# ethernet_chip.net
KiCad netlist of a schematic drawn in EAGLE
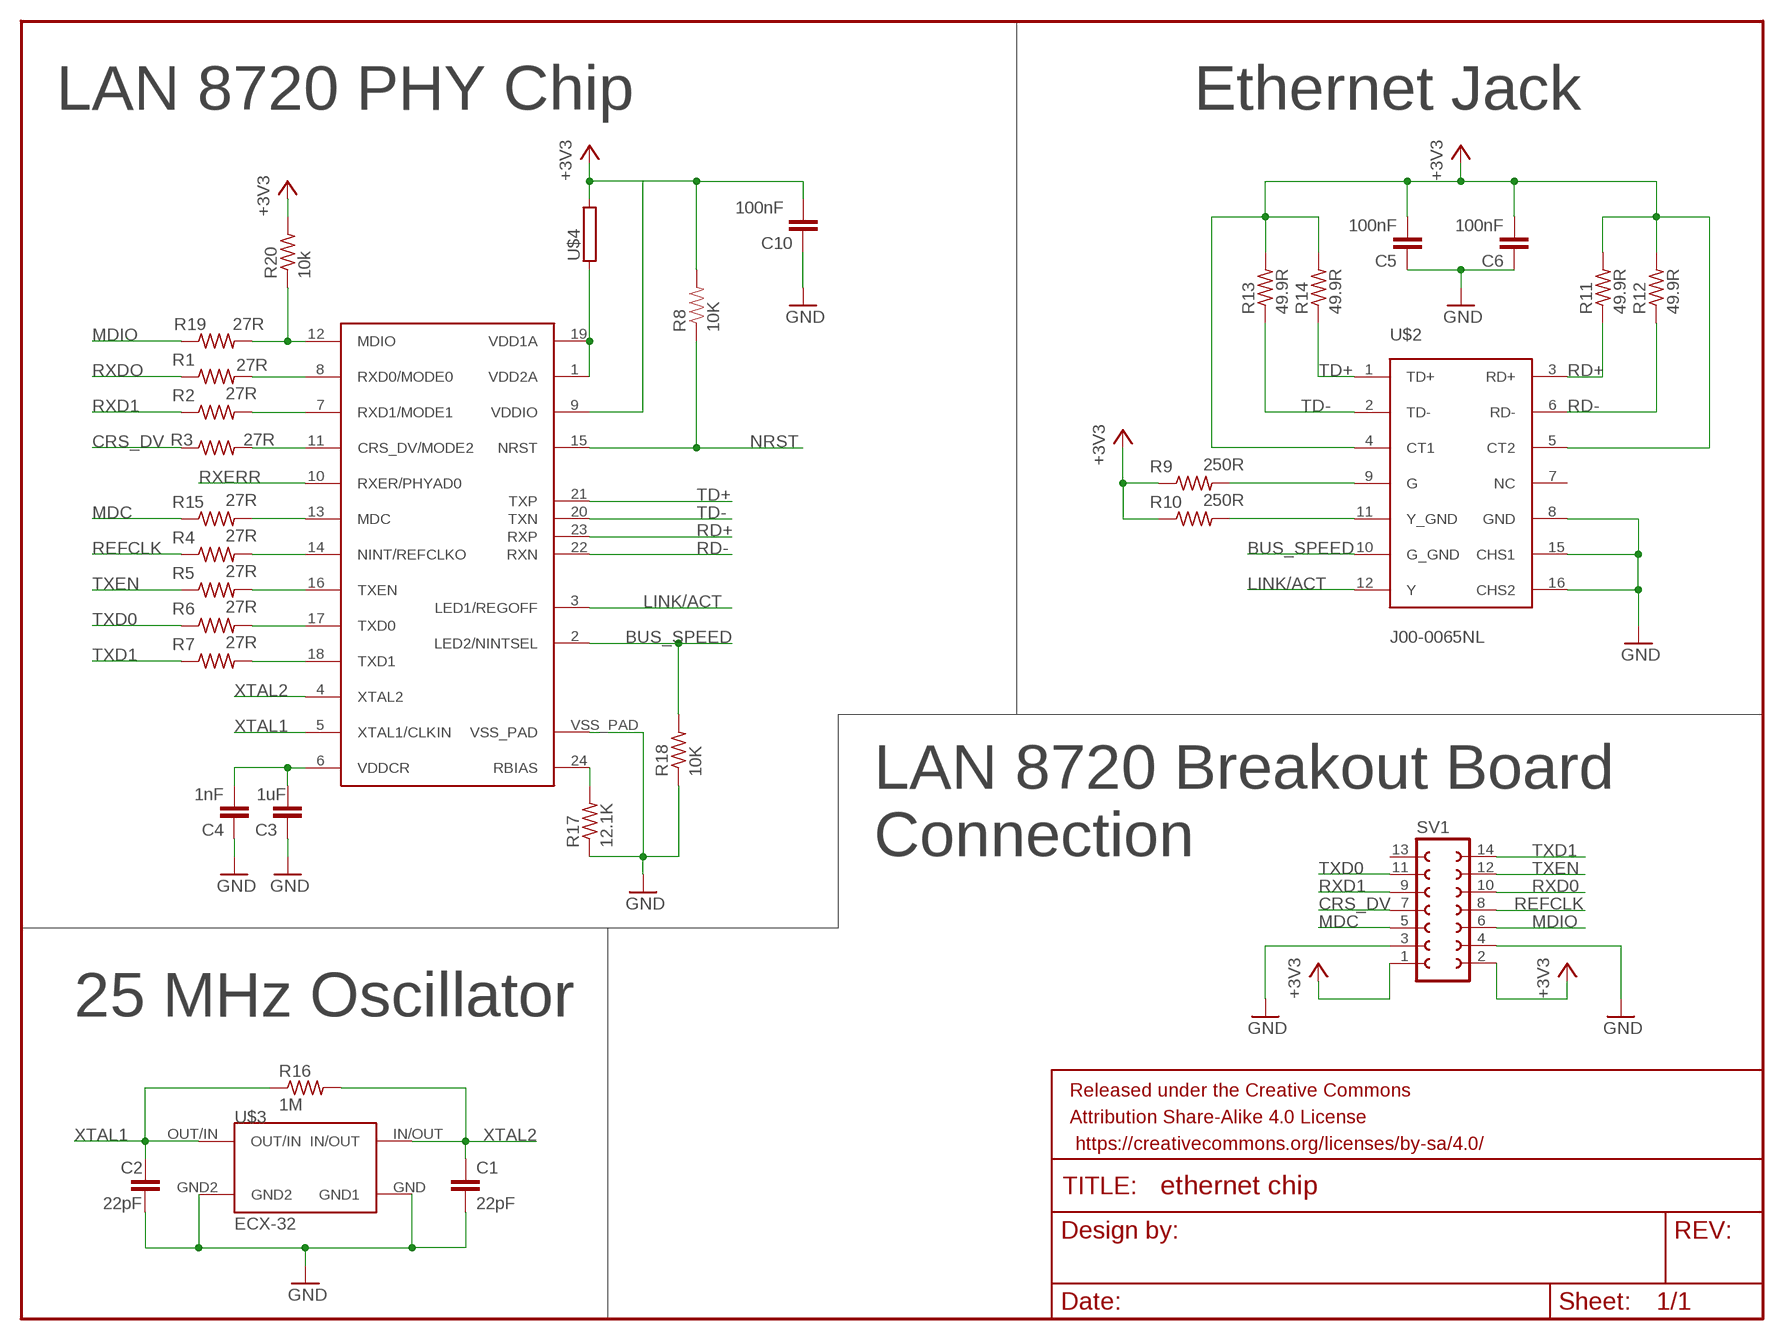
[diagram p0: schematic, sheet 1]

(export (version "E")
  (design (tool "Eeschema 10.0.6"))
  (components
    (comp (ref "C1")
      (value "22pF")
      (footprint "eagle-import:C0603")
      (libsource (lib "eagle-import") (part "CC0603"))
    )
    (comp (ref "C2")
      (value "22pF")
      (footprint "eagle-import:C0603")
      (libsource (lib "eagle-import") (part "CC0603"))
    )
    (comp (ref "C3")
      (value "1uF")
      (footprint "eagle-import:C0603")
      (libsource (lib "eagle-import") (part "CC0603"))
    )
    (comp (ref "C4")
      (value "1nF")
      (footprint "eagle-import:C0603")
      (libsource (lib "eagle-import") (part "CC0603"))
    )
    (comp (ref "C5")
      (value "100nF")
      (footprint "eagle-import:C0603")
      (libsource (lib "eagle-import") (part "CC0603"))
    )
    (comp (ref "C6")
      (value "100nF")
      (footprint "eagle-import:C0603")
      (libsource (lib "eagle-import") (part "CC0603"))
    )
    (comp (ref "C10")
      (value "100nF")
      (footprint "eagle-import:C0603")
      (libsource (lib "eagle-import") (part "CC0603"))
    )
    (comp (ref "FRAME1")
      (value "FRAME-LETTER")
      (footprint "eagle-import:CREATIVE_COMMONS")
      (libsource (lib "eagle-import") (part "FRAME-LETTER"))
    )
    (comp (ref "R1")
      (value "27R")
      (footprint "eagle-import:R0603")
      (libsource (lib "eagle-import") (part "R-US_R0603"))
    )
    (comp (ref "R2")
      (value "27R")
      (footprint "eagle-import:R0603")
      (libsource (lib "eagle-import") (part "R-US_R0603"))
    )
    (comp (ref "R3")
      (value "27R")
      (footprint "eagle-import:R0603")
      (libsource (lib "eagle-import") (part "R-US_R0603"))
    )
    (comp (ref "R4")
      (value "27R")
      (footprint "eagle-import:R0603")
      (libsource (lib "eagle-import") (part "R-US_R0603"))
    )
    (comp (ref "R5")
      (value "27R")
      (footprint "eagle-import:R0603")
      (libsource (lib "eagle-import") (part "R-US_R0603"))
    )
    (comp (ref "R6")
      (value "27R")
      (footprint "eagle-import:R0603")
      (libsource (lib "eagle-import") (part "R-US_R0603"))
    )
    (comp (ref "R7")
      (value "27R")
      (footprint "eagle-import:R0603")
      (libsource (lib "eagle-import") (part "R-US_R0603"))
    )
    (comp (ref "R8")
      (value "10K")
      (footprint "eagle-import:0603-RES")
      (libsource (lib "eagle-import") (part "RESISTOR0603-RES"))
    )
    (comp (ref "R9")
      (value "250R")
      (footprint "eagle-import:R0603")
      (libsource (lib "eagle-import") (part "R-US_R0603"))
    )
    (comp (ref "R10")
      (value "250R")
      (footprint "eagle-import:R0603")
      (libsource (lib "eagle-import") (part "R-US_R0603"))
    )
    (comp (ref "R11")
      (value "49.9R")
      (footprint "eagle-import:R0603")
      (libsource (lib "eagle-import") (part "R-US_R0603"))
    )
    (comp (ref "R12")
      (value "49.9R")
      (footprint "eagle-import:R0603")
      (libsource (lib "eagle-import") (part "R-US_R0603"))
    )
    (comp (ref "R13")
      (value "49.9R")
      (footprint "eagle-import:R0603")
      (libsource (lib "eagle-import") (part "R-US_R0603"))
    )
    (comp (ref "R14")
      (value "49.9R")
      (footprint "eagle-import:R0603")
      (libsource (lib "eagle-import") (part "R-US_R0603"))
    )
    (comp (ref "R15")
      (value "27R")
      (footprint "eagle-import:R0603")
      (libsource (lib "eagle-import") (part "R-US_R0603"))
    )
    (comp (ref "R16")
      (value "1M")
      (footprint "eagle-import:R0603")
      (libsource (lib "eagle-import") (part "R-US_R0603"))
    )
    (comp (ref "R17")
      (value "12.1K")
      (footprint "eagle-import:R0603")
      (libsource (lib "eagle-import") (part "R-US_R0603"))
    )
    (comp (ref "R18")
      (value "10K")
      (footprint "eagle-import:R0603")
      (libsource (lib "eagle-import") (part "R-US_R0603"))
    )
    (comp (ref "R19")
      (value "27R")
      (footprint "eagle-import:R0603")
      (libsource (lib "eagle-import") (part "R-US_R0603"))
    )
    (comp (ref "R20")
      (value "10k")
      (footprint "eagle-import:R0603")
      (libsource (lib "eagle-import") (part "R-US_R0603"))
    )
    (comp (ref "SV1")
      (value "FE07-2")
      (footprint "eagle-import:FE07-2")
      (libsource (lib "eagle-import") (part "FE07-2"))
    )
    (comp (ref "U$1")
      (value "LAN8720LAN8720")
      (footprint "eagle-import:24-QFN")
      (libsource (lib "eagle-import") (part "LAN8720LAN8720"))
    )
    (comp (ref "U$2")
      (value "J00-0065NL")
      (footprint "eagle-import:J00-0065NL")
      (libsource (lib "eagle-import") (part "J00-0065NL"))
    )
    (comp (ref "U$3")
      (value "ECX-32")
      (footprint "eagle-import:ECX-32")
      (libsource (lib "eagle-import") (part "ECX-32"))
    )
    (comp (ref "U$4")
      (value "553-2382-1-ND")
      (footprint "eagle-import:0603")
      (libsource (lib "eagle-import") (part "553-2382-1-ND"))
    )
  )
  (nets
    (net (code "1") (name "+3V3") (class "Default")
      (node (ref "C10") (pin "2") (pinfunction "2_2") (pintype "passive"))
      (node (ref "C5") (pin "2") (pinfunction "2_2") (pintype "passive"))
      (node (ref "C6") (pin "2") (pinfunction "2_2") (pintype "passive"))
      (node (ref "R10") (pin "1") (pinfunction "1_1") (pintype "passive"))
      (node (ref "R11") (pin "2") (pinfunction "2_2") (pintype "passive"))
      (node (ref "R12") (pin "2") (pinfunction "2_2") (pintype "passive"))
      (node (ref "R13") (pin "2") (pinfunction "2_2") (pintype "passive"))
      (node (ref "R14") (pin "2") (pinfunction "2_2") (pintype "passive"))
      (node (ref "R20") (pin "2") (pinfunction "2_2") (pintype "passive"))
      (node (ref "R8") (pin "2") (pinfunction "2_2") (pintype "passive"))
      (node (ref "R9") (pin "1") (pinfunction "1_1") (pintype "passive"))
      (node (ref "SV1") (pin "1") (pinfunction "1_1") (pintype "passive"))
      (node (ref "SV1") (pin "2") (pinfunction "2_2") (pintype "passive"))
      (node (ref "U$1") (pin "9") (pinfunction "VDDIO_9") (pintype "bidirectional"))
      (node (ref "U$2") (pin "4") (pinfunction "CT1_4") (pintype "bidirectional"))
      (node (ref "U$2") (pin "5") (pinfunction "CT2_5") (pintype "bidirectional"))
      (node (ref "U$4") (pin "2") (pinfunction "2_2") (pintype "passive"))
    )
    (net (code "2") (name "/BUS_SPEED") (class "Default")
      (node (ref "R18") (pin "2") (pinfunction "2_2") (pintype "passive"))
      (node (ref "U$1") (pin "2") (pinfunction "LED2/NINTSEL_2") (pintype "bidirectional"))
      (node (ref "U$2") (pin "10") (pinfunction "G_GND_10") (pintype "bidirectional"))
    )
    (net (code "3") (name "/CRS_DV") (class "Default")
      (node (ref "R3") (pin "1") (pinfunction "1_1") (pintype "passive"))
      (node (ref "SV1") (pin "7") (pinfunction "7_7") (pintype "passive"))
    )
    (net (code "4") (name "/LINK{slash}ACT") (class "Default")
      (node (ref "U$1") (pin "3") (pinfunction "LED1/REGOFF_3") (pintype "bidirectional"))
      (node (ref "U$2") (pin "12") (pinfunction "Y_12") (pintype "bidirectional"))
    )
    (net (code "5") (name "/MDC") (class "Default")
      (node (ref "R15") (pin "1") (pinfunction "1_1") (pintype "passive"))
      (node (ref "SV1") (pin "5") (pinfunction "5_5") (pintype "passive"))
    )
    (net (code "6") (name "/MDIO") (class "Default")
      (node (ref "R19") (pin "1") (pinfunction "1_1") (pintype "passive"))
      (node (ref "SV1") (pin "6") (pinfunction "6_6") (pintype "passive"))
    )
    (net (code "7") (name "/NRST") (class "Default")
      (node (ref "R8") (pin "1") (pinfunction "1_1") (pintype "passive"))
      (node (ref "U$1") (pin "15") (pinfunction "NRST_15") (pintype "bidirectional"))
    )
    (net (code "8") (name "/RD+") (class "Default")
      (node (ref "R11") (pin "1") (pinfunction "1_1") (pintype "passive"))
      (node (ref "U$1") (pin "23") (pinfunction "RXP_23") (pintype "bidirectional"))
      (node (ref "U$2") (pin "3") (pinfunction "RD+_3") (pintype "bidirectional"))
    )
    (net (code "9") (name "/RD-") (class "Default")
      (node (ref "R12") (pin "1") (pinfunction "1_1") (pintype "passive"))
      (node (ref "U$1") (pin "22") (pinfunction "RXN_22") (pintype "bidirectional"))
      (node (ref "U$2") (pin "6") (pinfunction "RD-_6") (pintype "bidirectional"))
    )
    (net (code "10") (name "/REFCLK") (class "Default")
      (node (ref "R4") (pin "1") (pinfunction "1_1") (pintype "passive"))
      (node (ref "SV1") (pin "8") (pinfunction "8_8") (pintype "passive"))
    )
    (net (code "11") (name "/RXD0") (class "Default")
      (node (ref "SV1") (pin "10") (pinfunction "10_10") (pintype "passive"))
    )
    (net (code "12") (name "/RXD1") (class "Default")
      (node (ref "R2") (pin "1") (pinfunction "1_1") (pintype "passive"))
      (node (ref "SV1") (pin "9") (pinfunction "9_9") (pintype "passive"))
    )
    (net (code "13") (name "/RXDO") (class "Default")
      (node (ref "R1") (pin "1") (pinfunction "1_1") (pintype "passive"))
    )
    (net (code "14") (name "/RXERR") (class "Default")
      (node (ref "U$1") (pin "10") (pinfunction "RXER/PHYAD0_10") (pintype "bidirectional"))
    )
    (net (code "15") (name "/TD+") (class "Default")
      (node (ref "R14") (pin "1") (pinfunction "1_1") (pintype "passive"))
      (node (ref "U$1") (pin "21") (pinfunction "TXP_21") (pintype "bidirectional"))
      (node (ref "U$2") (pin "1") (pinfunction "TD+_1") (pintype "bidirectional"))
    )
    (net (code "16") (name "/TD-") (class "Default")
      (node (ref "R13") (pin "1") (pinfunction "1_1") (pintype "passive"))
      (node (ref "U$1") (pin "20") (pinfunction "TXN_20") (pintype "bidirectional"))
      (node (ref "U$2") (pin "2") (pinfunction "TD-_2") (pintype "bidirectional"))
    )
    (net (code "17") (name "/TXD0") (class "Default")
      (node (ref "R6") (pin "1") (pinfunction "1_1") (pintype "passive"))
      (node (ref "SV1") (pin "11") (pinfunction "11_11") (pintype "passive"))
    )
    (net (code "18") (name "/TXD1") (class "Default")
      (node (ref "R7") (pin "1") (pinfunction "1_1") (pintype "passive"))
      (node (ref "SV1") (pin "14") (pinfunction "14_14") (pintype "passive"))
    )
    (net (code "19") (name "/TXEN") (class "Default")
      (node (ref "R5") (pin "1") (pinfunction "1_1") (pintype "passive"))
      (node (ref "SV1") (pin "12") (pinfunction "12_12") (pintype "passive"))
    )
    (net (code "20") (name "/XTAL1") (class "Default")
      (node (ref "C2") (pin "1") (pinfunction "1_1") (pintype "passive"))
      (node (ref "R16") (pin "1") (pinfunction "1_1") (pintype "passive"))
      (node (ref "U$1") (pin "5") (pinfunction "XTAL1/CLKIN_5") (pintype "bidirectional"))
      (node (ref "U$3") (pin "OUT/IN") (pinfunction "OUT/IN_OUT/IN") (pintype "bidirectional"))
    )
    (net (code "21") (name "/XTAL2") (class "Default")
      (node (ref "C1") (pin "1") (pinfunction "1_1") (pintype "passive"))
      (node (ref "R16") (pin "2") (pinfunction "2_2") (pintype "passive"))
      (node (ref "U$1") (pin "4") (pinfunction "XTAL2_4") (pintype "bidirectional"))
      (node (ref "U$3") (pin "IN/OUT") (pinfunction "IN/OUT_IN/OUT") (pintype "bidirectional"))
    )
    (net (code "22") (name "GND") (class "Default")
      (node (ref "C1") (pin "2") (pinfunction "2_2") (pintype "passive"))
      (node (ref "C10") (pin "1") (pinfunction "1_1") (pintype "passive"))
      (node (ref "C2") (pin "2") (pinfunction "2_2") (pintype "passive"))
      (node (ref "C3") (pin "1") (pinfunction "1_1") (pintype "passive"))
      (node (ref "C4") (pin "1") (pinfunction "1_1") (pintype "passive"))
      (node (ref "C5") (pin "1") (pinfunction "1_1") (pintype "passive"))
      (node (ref "C6") (pin "1") (pinfunction "1_1") (pintype "passive"))
      (node (ref "R17") (pin "1") (pinfunction "1_1") (pintype "passive"))
      (node (ref "R18") (pin "1") (pinfunction "1_1") (pintype "passive"))
      (node (ref "SV1") (pin "3") (pinfunction "3_3") (pintype "passive"))
      (node (ref "SV1") (pin "4") (pinfunction "4_4") (pintype "passive"))
      (node (ref "U$1") (pin "VSS_PAD") (pinfunction "VSS_PAD_VSS_PAD") (pintype "bidirectional"))
      (node (ref "U$2") (pin "15") (pinfunction "CHS1_15") (pintype "bidirectional"))
      (node (ref "U$2") (pin "16") (pinfunction "CHS2_16") (pintype "bidirectional"))
      (node (ref "U$2") (pin "8") (pinfunction "GND_8") (pintype "bidirectional"))
      (node (ref "U$3") (pin "GND") (pinfunction "GND1_GND") (pintype "bidirectional"))
      (node (ref "U$3") (pin "GND2") (pinfunction "GND2_GND2") (pintype "bidirectional"))
    )
    (net (code "23") (name "Net-(U$1-CRS_DV{slash}MODE2)") (class "Default")
      (node (ref "R3") (pin "2") (pinfunction "2_2") (pintype "passive"))
      (node (ref "U$1") (pin "11") (pinfunction "CRS_DV/MODE2_11") (pintype "bidirectional"))
    )
    (net (code "24") (name "Net-(U$1-MDC)") (class "Default")
      (node (ref "R15") (pin "2") (pinfunction "2_2") (pintype "passive"))
      (node (ref "U$1") (pin "13") (pinfunction "MDC_13") (pintype "bidirectional"))
    )
    (net (code "25") (name "Net-(U$1-MDIO)") (class "Default")
      (node (ref "R19") (pin "2") (pinfunction "2_2") (pintype "passive"))
      (node (ref "R20") (pin "1") (pinfunction "1_1") (pintype "passive"))
      (node (ref "U$1") (pin "12") (pinfunction "MDIO_12") (pintype "bidirectional"))
    )
    (net (code "26") (name "Net-(U$1-NINT{slash}REFCLKO)") (class "Default")
      (node (ref "R4") (pin "2") (pinfunction "2_2") (pintype "passive"))
      (node (ref "U$1") (pin "14") (pinfunction "NINT/REFCLKO_14") (pintype "bidirectional"))
    )
    (net (code "27") (name "Net-(U$1-RBIAS)") (class "Default")
      (node (ref "R17") (pin "2") (pinfunction "2_2") (pintype "passive"))
      (node (ref "U$1") (pin "24") (pinfunction "RBIAS_24") (pintype "bidirectional"))
    )
    (net (code "28") (name "Net-(U$1-RXD0{slash}MODE0)") (class "Default")
      (node (ref "R1") (pin "2") (pinfunction "2_2") (pintype "passive"))
      (node (ref "U$1") (pin "8") (pinfunction "RXD0/MODE0_8") (pintype "bidirectional"))
    )
    (net (code "29") (name "Net-(U$1-RXD1{slash}MODE1)") (class "Default")
      (node (ref "R2") (pin "2") (pinfunction "2_2") (pintype "passive"))
      (node (ref "U$1") (pin "7") (pinfunction "RXD1/MODE1_7") (pintype "bidirectional"))
    )
    (net (code "30") (name "Net-(U$1-TXD0)") (class "Default")
      (node (ref "R6") (pin "2") (pinfunction "2_2") (pintype "passive"))
      (node (ref "U$1") (pin "17") (pinfunction "TXD0_17") (pintype "bidirectional"))
    )
    (net (code "31") (name "Net-(U$1-TXD1)") (class "Default")
      (node (ref "R7") (pin "2") (pinfunction "2_2") (pintype "passive"))
      (node (ref "U$1") (pin "18") (pinfunction "TXD1_18") (pintype "bidirectional"))
    )
    (net (code "32") (name "Net-(U$1-TXEN)") (class "Default")
      (node (ref "R5") (pin "2") (pinfunction "2_2") (pintype "passive"))
      (node (ref "U$1") (pin "16") (pinfunction "TXEN_16") (pintype "bidirectional"))
    )
    (net (code "33") (name "Net-(U$1-VDD1A)") (class "Default")
      (node (ref "U$1") (pin "1") (pinfunction "VDD2A_1") (pintype "bidirectional"))
      (node (ref "U$1") (pin "19") (pinfunction "VDD1A_19") (pintype "bidirectional"))
      (node (ref "U$4") (pin "1") (pinfunction "1_1") (pintype "passive"))
    )
    (net (code "34") (name "Net-(U$1-VDDCR)") (class "Default")
      (node (ref "C3") (pin "2") (pinfunction "2_2") (pintype "passive"))
      (node (ref "C4") (pin "2") (pinfunction "2_2") (pintype "passive"))
      (node (ref "U$1") (pin "6") (pinfunction "VDDCR_6") (pintype "bidirectional"))
    )
    (net (code "35") (name "Net-(U$2-G)") (class "Default")
      (node (ref "R9") (pin "2") (pinfunction "2_2") (pintype "passive"))
      (node (ref "U$2") (pin "9") (pinfunction "G_9") (pintype "bidirectional"))
    )
    (net (code "36") (name "Net-(U$2-Y_GND)") (class "Default")
      (node (ref "R10") (pin "2") (pinfunction "2_2") (pintype "passive"))
      (node (ref "U$2") (pin "11") (pinfunction "Y_GND_11") (pintype "bidirectional"))
    )
    (net (code "37") (name "unconnected-(SV1-Pad13)") (class "Default")
      (node (ref "SV1") (pin "13") (pinfunction "13_13") (pintype "passive"))
    )
    (net (code "38") (name "unconnected-(U$2-NC-Pad7)") (class "Default")
      (node (ref "U$2") (pin "7") (pinfunction "NC_7") (pintype "bidirectional"))
    )
  )
)
